# Grove_-_IMU_10DOF_v1_1.net
KiCad netlist of a schematic drawn in EAGLE
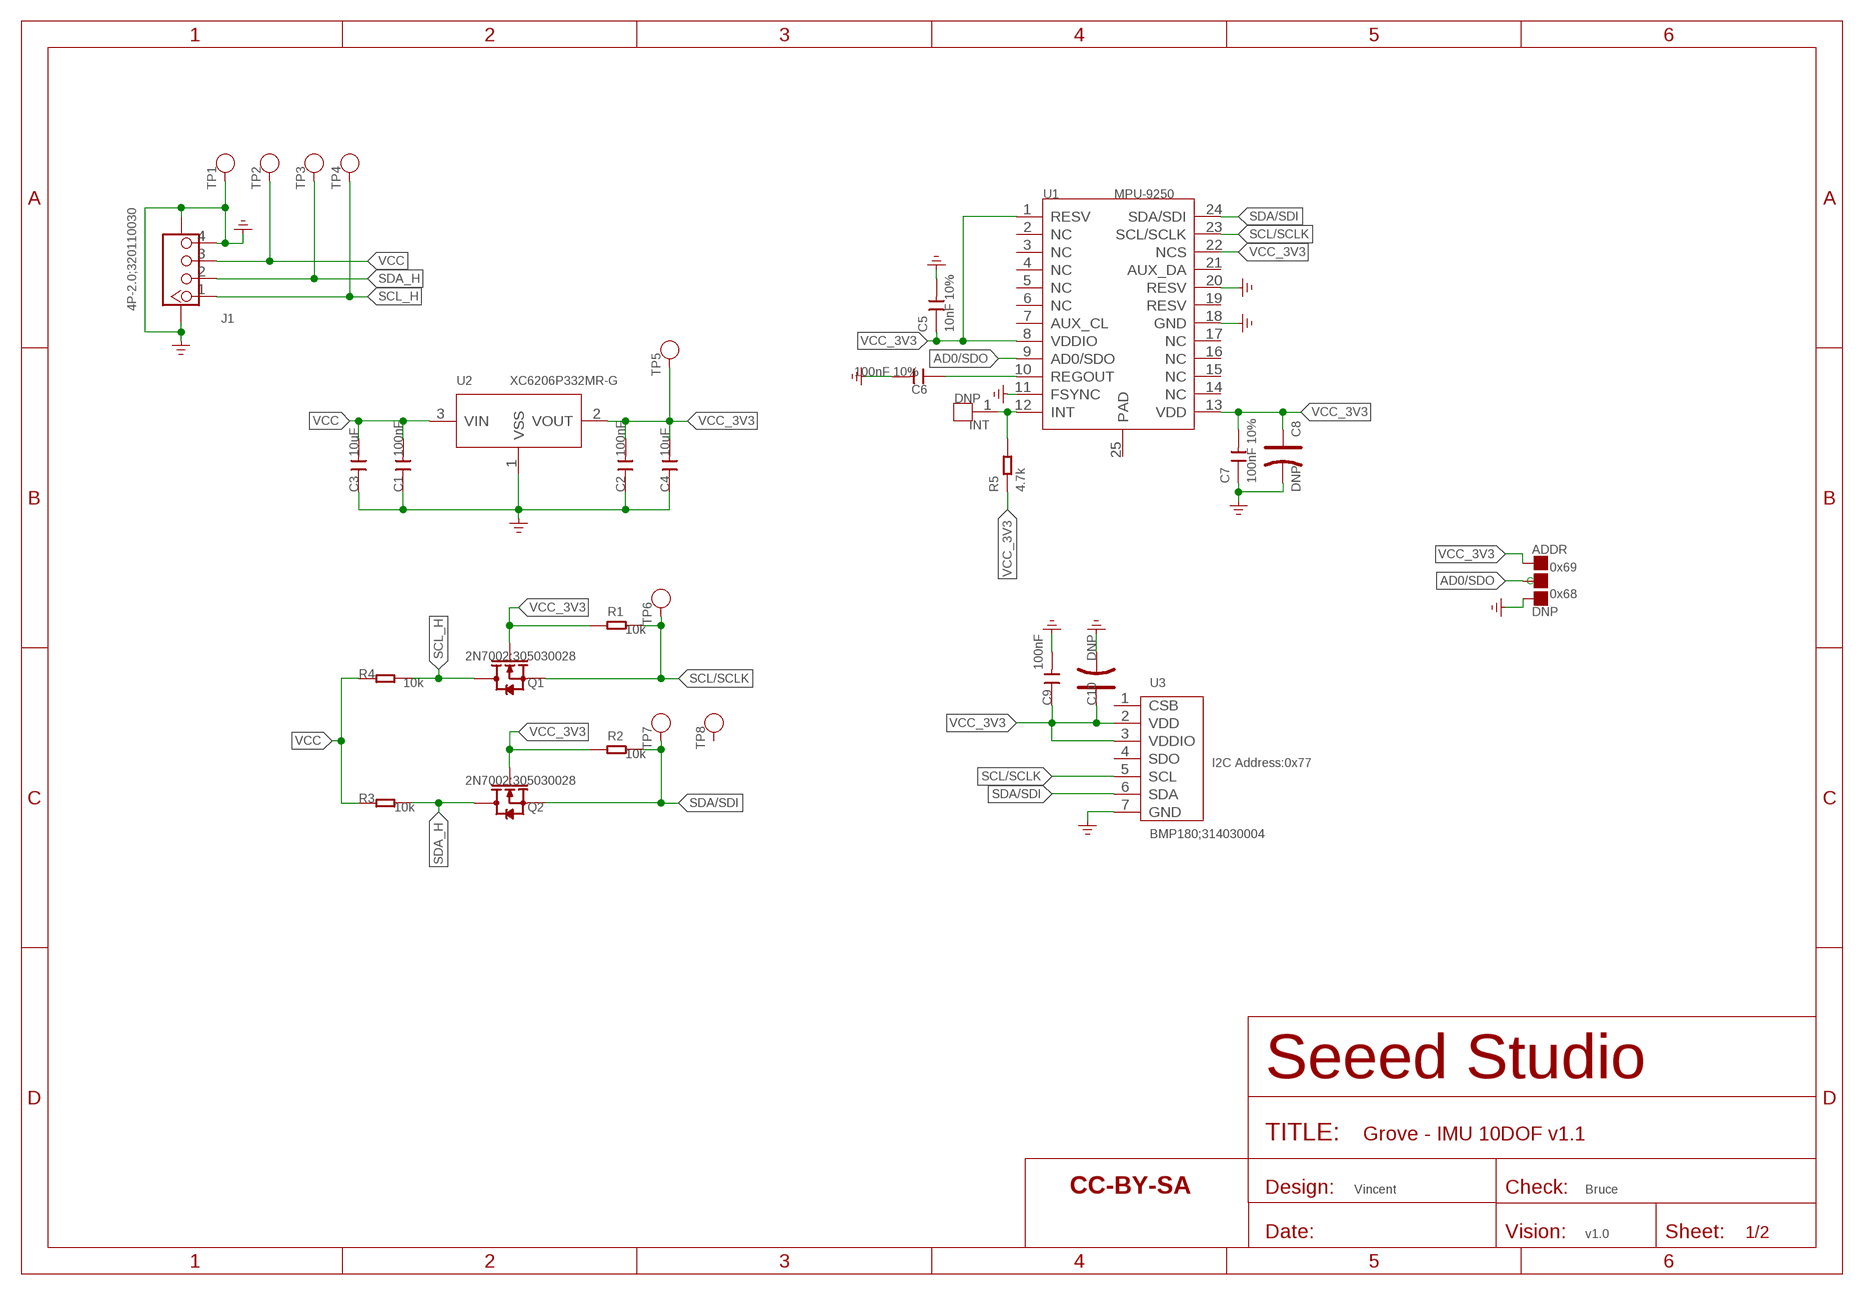
[diagram p0: schematic, sheet 1]

(export (version "E")
  (design (tool "Eeschema 10.0.6"))
  (components
    (comp (ref "ADDR")
      (value "DNP")
      (footprint "eagle-import:3P-SMD-L4.1_W1.5MM")
      (libsource (lib "eagle-import") (part "PAD-JUMPER-3P-4040"))
    )
    (comp (ref "C1")
      (value "100nF")
      (footprint "eagle-import:C0603")
      (libsource (lib "eagle-import") (part "CAP-0603"))
    )
    (comp (ref "C2")
      (value "100nF")
      (footprint "eagle-import:C0603")
      (libsource (lib "eagle-import") (part "CAP-0603"))
    )
    (comp (ref "C3")
      (value "10uF")
      (footprint "eagle-import:C0805")
      (libsource (lib "eagle-import") (part "CAP-0805"))
    )
    (comp (ref "C4")
      (value "10uF")
      (footprint "eagle-import:C0805")
      (libsource (lib "eagle-import") (part "CAP-0805"))
    )
    (comp (ref "C5")
      (value "10nF 10%")
      (footprint "eagle-import:C0603")
      (libsource (lib "eagle-import") (part "CAP-0603"))
    )
    (comp (ref "C6")
      (value "100nF 10%")
      (footprint "eagle-import:C0603")
      (libsource (lib "eagle-import") (part "CAP-0603"))
    )
    (comp (ref "C7")
      (value "100nF 10%")
      (footprint "eagle-import:C0603")
      (libsource (lib "eagle-import") (part "CAP-0603"))
    )
    (comp (ref "C8")
      (value "DNP")
      (footprint "eagle-import:AVX-A")
      (libsource (lib "eagle-import") (part "CAP-POLAR-AVX-A"))
    )
    (comp (ref "C9")
      (value "100nF")
      (footprint "eagle-import:C0603")
      (libsource (lib "eagle-import") (part "CAP-0603"))
    )
    (comp (ref "C10")
      (value "DNP")
      (footprint "eagle-import:AVX-A")
      (libsource (lib "eagle-import") (part "CAP-POLAR-AVX-A"))
    )
    (comp (ref "INT")
      (value "DNP")
      (footprint "eagle-import:1P-65_35MIL")
      (libsource (lib "eagle-import") (part "HEADER-1P-35"))
    )
    (comp (ref "J1")
      (value "4P-2.0;320110030")
      (footprint "eagle-import:4P-SMD-2.0")
      (libsource (lib "eagle-import") (part "GROVE-CONNECTOR-SMD'DD'"))
    )
    (comp (ref "Q1")
      (value "2N7002;305030028")
      (footprint "eagle-import:SOT-23")
      (libsource (lib "eagle-import") (part "MOSFET-N'SOT23'"))
    )
    (comp (ref "Q2")
      (value "2N7002;305030028")
      (footprint "eagle-import:SOT-23")
      (libsource (lib "eagle-import") (part "MOSFET-N'SOT23'"))
    )
    (comp (ref "R1")
      (value "10k")
      (footprint "eagle-import:R0603")
      (libsource (lib "eagle-import") (part "RES-0603"))
    )
    (comp (ref "R2")
      (value "10k")
      (footprint "eagle-import:R0603")
      (libsource (lib "eagle-import") (part "RES-0603"))
    )
    (comp (ref "R3")
      (value "10k")
      (footprint "eagle-import:R0603")
      (libsource (lib "eagle-import") (part "RES-0603"))
    )
    (comp (ref "R4")
      (value "10k")
      (footprint "eagle-import:R0603")
      (libsource (lib "eagle-import") (part "RES-0603"))
    )
    (comp (ref "R5")
      (value "4.7k")
      (footprint "eagle-import:R0603")
      (libsource (lib "eagle-import") (part "RES-0603"))
    )
    (comp (ref "TP1")
      (value "DNP")
      (footprint "eagle-import:TP-D45MIL")
      (libsource (lib "eagle-import") (part "PAD-TEST-POINT'4545'"))
    )
    (comp (ref "TP2")
      (value "DNP")
      (footprint "eagle-import:TP-D45MIL")
      (libsource (lib "eagle-import") (part "PAD-TEST-POINT'4545'"))
    )
    (comp (ref "TP3")
      (value "DNP")
      (footprint "eagle-import:TP-D45MIL")
      (libsource (lib "eagle-import") (part "PAD-TEST-POINT'4545'"))
    )
    (comp (ref "TP4")
      (value "DNP")
      (footprint "eagle-import:TP-D45MIL")
      (libsource (lib "eagle-import") (part "PAD-TEST-POINT'4545'"))
    )
    (comp (ref "TP5")
      (value "DNP")
      (footprint "eagle-import:TP-D45MIL")
      (libsource (lib "eagle-import") (part "PAD-TEST-POINT'4545'"))
    )
    (comp (ref "TP6")
      (value "DNP")
      (footprint "eagle-import:TP-D45MIL")
      (libsource (lib "eagle-import") (part "PAD-TEST-POINT'4545'"))
    )
    (comp (ref "TP7")
      (value "DNP")
      (footprint "eagle-import:TP-D45MIL")
      (libsource (lib "eagle-import") (part "PAD-TEST-POINT'4545'"))
    )
    (comp (ref "TP8")
      (value "DNP")
      (footprint "eagle-import:TP-D45MIL")
      (libsource (lib "eagle-import") (part "PAD-TEST-POINT'4545'"))
    )
    (comp (ref "U$1")
      (value "SEEEDSTUDIO-OPEN-SCH-FRAME")
      (footprint "eagle-import:SEEEDSTUDIO-PCB-FRAME")
      (libsource (lib "eagle-import") (part "SEEEDSTUDIO-OPEN-SCH-FRAME"))
    )
    (comp (ref "U1")
      (value "MPU-9250")
      (footprint "eagle-import:LEAD-QFN24")
      (libsource (lib "eagle-import") (part "MPU-9250"))
    )
    (comp (ref "U2")
      (value "XC6206P332MR-G")
      (footprint "eagle-import:SOT-23")
      (libsource (lib "eagle-import") (part "PMIC-XC6206PMR"))
    )
    (comp (ref "U3")
      (value "BMP180;314030004")
      (footprint "eagle-import:LGA-7")
      (libsource (lib "eagle-import") (part "BMP180"))
    )
  )
  (nets
    (net (code "1") (name "AD0{slash}SDO") (class "Default")
      (node (ref "ADDR") (pin "MM") (pinfunction "C_MM") (pintype "bidirectional"))
      (node (ref "U1") (pin "9") (pinfunction "AD0/SDO_9") (pintype "bidirectional"))
    )
    (net (code "2") (name "GND") (class "Default")
      (node (ref "ADDR") (pin "11") (pinfunction "R_11") (pintype "bidirectional"))
      (node (ref "C1") (pin "1") (pinfunction "1_1") (pintype "passive"))
      (node (ref "C10") (pin "-") (pinfunction "-_-") (pintype "passive"))
      (node (ref "C2") (pin "1") (pinfunction "1_1") (pintype "passive"))
      (node (ref "C3") (pin "1") (pinfunction "1_1") (pintype "passive"))
      (node (ref "C4") (pin "1") (pinfunction "1_1") (pintype "passive"))
      (node (ref "C5") (pin "2") (pinfunction "2_2") (pintype "passive"))
      (node (ref "C6") (pin "2") (pinfunction "2_2") (pintype "passive"))
      (node (ref "C7") (pin "1") (pinfunction "1_1") (pintype "passive"))
      (node (ref "C8") (pin "-") (pinfunction "-_-") (pintype "passive"))
      (node (ref "C9") (pin "2") (pinfunction "2_2") (pintype "passive"))
      (node (ref "J1") (pin "4") (pinfunction "4_4") (pintype "bidirectional"))
      (node (ref "J1") (pin "SS1") (pinfunction "SS1_SS1") (pintype "bidirectional"))
      (node (ref "J1") (pin "SS2") (pinfunction "SS2_SS2") (pintype "bidirectional"))
      (node (ref "TP1") (pin "T") (pinfunction "T_T") (pintype "bidirectional"))
      (node (ref "U1") (pin "11") (pinfunction "FSYNC_11") (pintype "bidirectional"))
      (node (ref "U1") (pin "18") (pinfunction "GND_18") (pintype "bidirectional"))
      (node (ref "U1") (pin "20") (pinfunction "RESV_20") (pintype "bidirectional"))
      (node (ref "U2") (pin "1") (pinfunction "VSS_1") (pintype "power_in"))
      (node (ref "U3") (pin "7") (pinfunction "GND_7") (pintype "bidirectional"))
    )
    (net (code "3") (name "Net-(U1-INT)") (class "Default")
      (node (ref "INT") (pin "1") (pinfunction "1_1") (pintype "bidirectional"))
      (node (ref "R5") (pin "2") (pinfunction "2_2") (pintype "passive"))
      (node (ref "U1") (pin "12") (pinfunction "INT_12") (pintype "bidirectional"))
    )
    (net (code "4") (name "Net-(U1-REGOUT)") (class "Default")
      (node (ref "C6") (pin "1") (pinfunction "1_1") (pintype "passive"))
      (node (ref "U1") (pin "10") (pinfunction "REGOUT_10") (pintype "bidirectional"))
    )
    (net (code "5") (name "SCL_H") (class "Default")
      (node (ref "J1") (pin "1") (pinfunction "1_1") (pintype "bidirectional"))
      (node (ref "Q1") (pin "3") (pinfunction "D_3") (pintype "passive"))
      (node (ref "R4") (pin "2") (pinfunction "2_2") (pintype "passive"))
      (node (ref "TP4") (pin "T") (pinfunction "T_T") (pintype "bidirectional"))
    )
    (net (code "6") (name "SCL{slash}SCLK") (class "Default")
      (node (ref "Q1") (pin "2") (pinfunction "S_2") (pintype "passive"))
      (node (ref "R1") (pin "2") (pinfunction "2_2") (pintype "passive"))
      (node (ref "TP6") (pin "T") (pinfunction "T_T") (pintype "bidirectional"))
      (node (ref "U1") (pin "23") (pinfunction "SCL/SCLK_23") (pintype "bidirectional"))
      (node (ref "U3") (pin "5") (pinfunction "SCL_5") (pintype "bidirectional"))
    )
    (net (code "7") (name "SDA_H") (class "Default")
      (node (ref "J1") (pin "2") (pinfunction "2_2") (pintype "bidirectional"))
      (node (ref "Q2") (pin "3") (pinfunction "D_3") (pintype "passive"))
      (node (ref "R3") (pin "2") (pinfunction "2_2") (pintype "passive"))
      (node (ref "TP3") (pin "T") (pinfunction "T_T") (pintype "bidirectional"))
    )
    (net (code "8") (name "SDA{slash}SDI") (class "Default")
      (node (ref "Q2") (pin "2") (pinfunction "S_2") (pintype "passive"))
      (node (ref "R2") (pin "2") (pinfunction "2_2") (pintype "passive"))
      (node (ref "TP7") (pin "T") (pinfunction "T_T") (pintype "bidirectional"))
      (node (ref "U1") (pin "24") (pinfunction "SDA/SDI_24") (pintype "bidirectional"))
      (node (ref "U3") (pin "6") (pinfunction "SDA_6") (pintype "bidirectional"))
    )
    (net (code "9") (name "VCC") (class "Default")
      (node (ref "C1") (pin "2") (pinfunction "2_2") (pintype "passive"))
      (node (ref "C3") (pin "2") (pinfunction "2_2") (pintype "passive"))
      (node (ref "J1") (pin "3") (pinfunction "3_3") (pintype "bidirectional"))
      (node (ref "R3") (pin "1") (pinfunction "1_1") (pintype "passive"))
      (node (ref "R4") (pin "1") (pinfunction "1_1") (pintype "passive"))
      (node (ref "TP2") (pin "T") (pinfunction "T_T") (pintype "bidirectional"))
      (node (ref "U2") (pin "3") (pinfunction "VIN_3") (pintype "input"))
    )
    (net (code "10") (name "VCC_3V3") (class "Default")
      (node (ref "ADDR") (pin "00") (pinfunction "L_00") (pintype "bidirectional"))
      (node (ref "C10") (pin "+") (pinfunction "+_+") (pintype "passive"))
      (node (ref "C2") (pin "2") (pinfunction "2_2") (pintype "passive"))
      (node (ref "C4") (pin "2") (pinfunction "2_2") (pintype "passive"))
      (node (ref "C5") (pin "1") (pinfunction "1_1") (pintype "passive"))
      (node (ref "C7") (pin "2") (pinfunction "2_2") (pintype "passive"))
      (node (ref "C8") (pin "+") (pinfunction "+_+") (pintype "passive"))
      (node (ref "C9") (pin "1") (pinfunction "1_1") (pintype "passive"))
      (node (ref "Q1") (pin "1") (pinfunction "G_1") (pintype "passive"))
      (node (ref "Q2") (pin "1") (pinfunction "G_1") (pintype "passive"))
      (node (ref "R1") (pin "1") (pinfunction "1_1") (pintype "passive"))
      (node (ref "R2") (pin "1") (pinfunction "1_1") (pintype "passive"))
      (node (ref "R5") (pin "1") (pinfunction "1_1") (pintype "passive"))
      (node (ref "TP5") (pin "T") (pinfunction "T_T") (pintype "bidirectional"))
      (node (ref "U1") (pin "1") (pinfunction "RESV_1") (pintype "bidirectional"))
      (node (ref "U1") (pin "13") (pinfunction "VDD_13") (pintype "bidirectional"))
      (node (ref "U1") (pin "22") (pinfunction "NCS_22") (pintype "bidirectional"))
      (node (ref "U1") (pin "8") (pinfunction "VDDIO_8") (pintype "bidirectional"))
      (node (ref "U2") (pin "2") (pinfunction "VOUT_2") (pintype "output"))
      (node (ref "U3") (pin "2") (pinfunction "VDD_2") (pintype "bidirectional"))
      (node (ref "U3") (pin "3") (pinfunction "VDDIO_3") (pintype "bidirectional"))
    )
    (net (code "11") (name "unconnected-(TP8-PadT)") (class "Default")
      (node (ref "TP8") (pin "T") (pinfunction "T_T") (pintype "bidirectional"))
    )
    (net (code "12") (name "unconnected-(U1-AUX_CL-Pad7)") (class "Default")
      (node (ref "U1") (pin "7") (pinfunction "AUX_CL_7") (pintype "bidirectional"))
    )
    (net (code "13") (name "unconnected-(U1-AUX_DA-Pad21)") (class "Default")
      (node (ref "U1") (pin "21") (pinfunction "AUX_DA_21") (pintype "bidirectional"))
    )
    (net (code "14") (name "unconnected-(U1-NC-Pad2)") (class "Default")
      (node (ref "U1") (pin "2") (pinfunction "NC_2") (pintype "bidirectional"))
    )
    (net (code "15") (name "unconnected-(U1-NC-Pad3)") (class "Default")
      (node (ref "U1") (pin "3") (pinfunction "NC_3") (pintype "bidirectional"))
    )
    (net (code "16") (name "unconnected-(U1-NC-Pad4)") (class "Default")
      (node (ref "U1") (pin "4") (pinfunction "NC_4") (pintype "bidirectional"))
    )
    (net (code "17") (name "unconnected-(U1-NC-Pad5)") (class "Default")
      (node (ref "U1") (pin "5") (pinfunction "NC_5") (pintype "bidirectional"))
    )
    (net (code "18") (name "unconnected-(U1-NC-Pad6)") (class "Default")
      (node (ref "U1") (pin "6") (pinfunction "NC_6") (pintype "bidirectional"))
    )
    (net (code "19") (name "unconnected-(U1-NC-Pad14)") (class "Default")
      (node (ref "U1") (pin "14") (pinfunction "NC_14") (pintype "bidirectional"))
    )
    (net (code "20") (name "unconnected-(U1-NC-Pad15)") (class "Default")
      (node (ref "U1") (pin "15") (pinfunction "NC_15") (pintype "bidirectional"))
    )
    (net (code "21") (name "unconnected-(U1-NC-Pad16)") (class "Default")
      (node (ref "U1") (pin "16") (pinfunction "NC_16") (pintype "bidirectional"))
    )
    (net (code "22") (name "unconnected-(U1-NC-Pad17)") (class "Default")
      (node (ref "U1") (pin "17") (pinfunction "NC_17") (pintype "bidirectional"))
    )
    (net (code "23") (name "unconnected-(U1-PAD-Pad25)") (class "Default")
      (node (ref "U1") (pin "25") (pinfunction "PAD_25") (pintype "bidirectional"))
    )
    (net (code "24") (name "unconnected-(U1-RESV-Pad19)") (class "Default")
      (node (ref "U1") (pin "19") (pinfunction "RESV_19") (pintype "bidirectional"))
    )
    (net (code "25") (name "unconnected-(U3-CSB-Pad1)") (class "Default")
      (node (ref "U3") (pin "1") (pinfunction "CSB_1") (pintype "bidirectional"))
    )
    (net (code "26") (name "unconnected-(U3-SDO-Pad4)") (class "Default")
      (node (ref "U3") (pin "4") (pinfunction "SDO_4") (pintype "bidirectional"))
    )
  )
)
